# Encodeurs_Schematic.net
KiCad netlist of a schematic drawn in Altium Designer
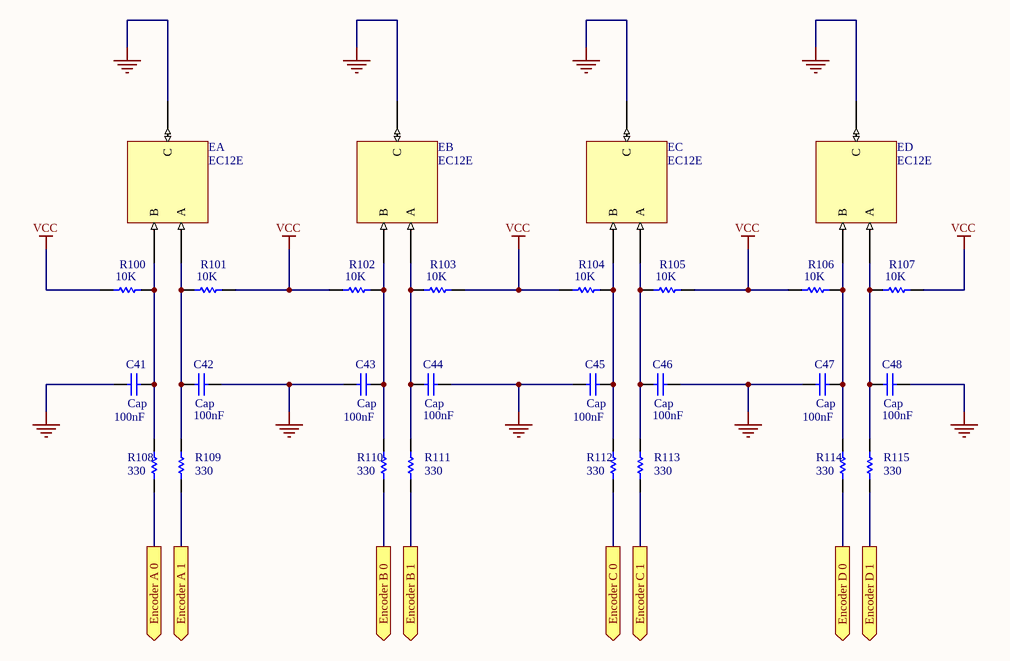
[diagram p0: Encodeurs.Schematic.SchDoc]

(export (version "E")
  (design (tool "Eeschema 10.0.6"))
  (components
    (comp (ref "C41")
      (value "Cap")
      (footprint "CAPC1608N")
      (description "Capacitor")
      (fields (field (name "ALTIUM_VALUE") "100nF") (field (name "PUBLISHER") "Altium Limited"))
      (libsource (lib "Miscellaneous Devices") (part "Cap"))
    )
    (comp (ref "C42")
      (value "Cap")
      (footprint "CAPC1608N")
      (description "Capacitor")
      (fields (field (name "ALTIUM_VALUE") "100nF") (field (name "PUBLISHER") "Altium Limited"))
      (libsource (lib "Miscellaneous Devices") (part "Cap"))
    )
    (comp (ref "C43")
      (value "Cap")
      (footprint "CAPC1608N")
      (description "Capacitor")
      (fields (field (name "ALTIUM_VALUE") "100nF") (field (name "PUBLISHER") "Altium Limited"))
      (libsource (lib "Miscellaneous Devices") (part "Cap"))
    )
    (comp (ref "C44")
      (value "Cap")
      (footprint "CAPC1608N")
      (description "Capacitor")
      (fields (field (name "ALTIUM_VALUE") "100nF") (field (name "PUBLISHER") "Altium Limited"))
      (libsource (lib "Miscellaneous Devices") (part "Cap"))
    )
    (comp (ref "C45")
      (value "Cap")
      (footprint "CAPC1608N")
      (description "Capacitor")
      (fields (field (name "ALTIUM_VALUE") "100nF") (field (name "PUBLISHER") "Altium Limited"))
      (libsource (lib "Miscellaneous Devices") (part "Cap"))
    )
    (comp (ref "C46")
      (value "Cap")
      (footprint "CAPC1608N")
      (description "Capacitor")
      (fields (field (name "ALTIUM_VALUE") "100nF") (field (name "PUBLISHER") "Altium Limited"))
      (libsource (lib "Miscellaneous Devices") (part "Cap"))
    )
    (comp (ref "C47")
      (value "Cap")
      (footprint "CAPC1608N")
      (description "Capacitor")
      (fields (field (name "ALTIUM_VALUE") "100nF") (field (name "PUBLISHER") "Altium Limited"))
      (libsource (lib "Miscellaneous Devices") (part "Cap"))
    )
    (comp (ref "C48")
      (value "Cap")
      (footprint "CAPC1608N")
      (description "Capacitor")
      (fields (field (name "ALTIUM_VALUE") "100nF") (field (name "PUBLISHER") "Altium Limited"))
      (libsource (lib "Miscellaneous Devices") (part "Cap"))
    )
    (comp (ref "EA")
      (value "EC12E")
      (footprint "EC12E")
      (libsource (lib "SynthyTwo.Components") (part "EC12E"))
    )
    (comp (ref "EB")
      (value "EC12E")
      (footprint "EC12E")
      (libsource (lib "SynthyTwo.Components") (part "EC12E"))
    )
    (comp (ref "EC")
      (value "EC12E")
      (footprint "EC12E")
      (libsource (lib "SynthyTwo.Components") (part "EC12E"))
    )
    (comp (ref "ED")
      (value "EC12E")
      (footprint "EC12E")
      (libsource (lib "SynthyTwo.Components") (part "EC12E"))
    )
    (comp (ref "R100")
      (value "10K")
      (footprint "CAPC1608N")
      (description "Resistor")
      (fields (field (name "PUBLISHER") "Altium Limited"))
      (libsource (lib "Miscellaneous Devices") (part "Res1"))
    )
    (comp (ref "R101")
      (value "10K")
      (footprint "CAPC1608N")
      (description "Resistor")
      (fields (field (name "PUBLISHER") "Altium Limited"))
      (libsource (lib "Miscellaneous Devices") (part "Res1"))
    )
    (comp (ref "R102")
      (value "10K")
      (footprint "CAPC1608N")
      (description "Resistor")
      (fields (field (name "PUBLISHER") "Altium Limited"))
      (libsource (lib "Miscellaneous Devices") (part "Res1"))
    )
    (comp (ref "R103")
      (value "10K")
      (footprint "CAPC1608N")
      (description "Resistor")
      (fields (field (name "PUBLISHER") "Altium Limited"))
      (libsource (lib "Miscellaneous Devices") (part "Res1"))
    )
    (comp (ref "R104")
      (value "10K")
      (footprint "CAPC1608N")
      (description "Resistor")
      (fields (field (name "PUBLISHER") "Altium Limited"))
      (libsource (lib "Miscellaneous Devices") (part "Res1"))
    )
    (comp (ref "R105")
      (value "10K")
      (footprint "CAPC1608N")
      (description "Resistor")
      (fields (field (name "PUBLISHER") "Altium Limited"))
      (libsource (lib "Miscellaneous Devices") (part "Res1"))
    )
    (comp (ref "R106")
      (value "10K")
      (footprint "CAPC1608N")
      (description "Resistor")
      (fields (field (name "PUBLISHER") "Altium Limited"))
      (libsource (lib "Miscellaneous Devices") (part "Res1"))
    )
    (comp (ref "R107")
      (value "10K")
      (footprint "CAPC1608N")
      (description "Resistor")
      (fields (field (name "PUBLISHER") "Altium Limited"))
      (libsource (lib "Miscellaneous Devices") (part "Res1"))
    )
    (comp (ref "R108")
      (value "330")
      (footprint "CAPC1608N")
      (description "Resistor")
      (fields (field (name "PUBLISHER") "Altium Limited"))
      (libsource (lib "Miscellaneous Devices") (part "Res1"))
    )
    (comp (ref "R109")
      (value "330")
      (footprint "CAPC1608N")
      (description "Resistor")
      (fields (field (name "PUBLISHER") "Altium Limited"))
      (libsource (lib "Miscellaneous Devices") (part "Res1"))
    )
    (comp (ref "R110")
      (value "330")
      (footprint "CAPC1608N")
      (description "Resistor")
      (fields (field (name "PUBLISHER") "Altium Limited"))
      (libsource (lib "Miscellaneous Devices") (part "Res1"))
    )
    (comp (ref "R111")
      (value "330")
      (footprint "CAPC1608N")
      (description "Resistor")
      (fields (field (name "PUBLISHER") "Altium Limited"))
      (libsource (lib "Miscellaneous Devices") (part "Res1"))
    )
    (comp (ref "R112")
      (value "330")
      (footprint "CAPC1608N")
      (description "Resistor")
      (fields (field (name "PUBLISHER") "Altium Limited"))
      (libsource (lib "Miscellaneous Devices") (part "Res1"))
    )
    (comp (ref "R113")
      (value "330")
      (footprint "CAPC1608N")
      (description "Resistor")
      (fields (field (name "PUBLISHER") "Altium Limited"))
      (libsource (lib "Miscellaneous Devices") (part "Res1"))
    )
    (comp (ref "R114")
      (value "330")
      (footprint "CAPC1608N")
      (description "Resistor")
      (fields (field (name "PUBLISHER") "Altium Limited"))
      (libsource (lib "Miscellaneous Devices") (part "Res1"))
    )
    (comp (ref "R115")
      (value "330")
      (footprint "CAPC1608N")
      (description "Resistor")
      (fields (field (name "PUBLISHER") "Altium Limited"))
      (libsource (lib "Miscellaneous Devices") (part "Res1"))
    )
  )
  (nets
    (net (code "1") (name "/Encoder A 0") (class "Default")
      (node (ref "R108") (pin "1") (pinfunction "1_1") (pintype "passive"))
    )
    (net (code "2") (name "/Encoder A 1") (class "Default")
      (node (ref "R109") (pin "1") (pinfunction "1_1") (pintype "passive"))
    )
    (net (code "3") (name "/Encoder B 0") (class "Default")
      (node (ref "R110") (pin "1") (pinfunction "1_1") (pintype "passive"))
    )
    (net (code "4") (name "/Encoder B 1") (class "Default")
      (node (ref "R111") (pin "1") (pinfunction "1_1") (pintype "passive"))
    )
    (net (code "5") (name "/Encoder C 0") (class "Default")
      (node (ref "R112") (pin "1") (pinfunction "1_1") (pintype "passive"))
    )
    (net (code "6") (name "/Encoder C 1") (class "Default")
      (node (ref "R113") (pin "1") (pinfunction "1_1") (pintype "passive"))
    )
    (net (code "7") (name "/Encoder D 0") (class "Default")
      (node (ref "R114") (pin "1") (pinfunction "1_1") (pintype "passive"))
    )
    (net (code "8") (name "/Encoder D 1") (class "Default")
      (node (ref "R115") (pin "1") (pinfunction "1_1") (pintype "passive"))
    )
    (net (code "9") (name "GND") (class "Default")
      (node (ref "C41") (pin "1") (pinfunction "1_1") (pintype "passive"))
      (node (ref "C42") (pin "1") (pinfunction "1_1") (pintype "passive"))
      (node (ref "C43") (pin "1") (pinfunction "1_1") (pintype "passive"))
      (node (ref "C44") (pin "1") (pinfunction "1_1") (pintype "passive"))
      (node (ref "C45") (pin "1") (pinfunction "1_1") (pintype "passive"))
      (node (ref "C46") (pin "1") (pinfunction "1_1") (pintype "passive"))
      (node (ref "C47") (pin "1") (pinfunction "1_1") (pintype "passive"))
      (node (ref "C48") (pin "1") (pinfunction "1_1") (pintype "passive"))
      (node (ref "EA") (pin "GND") (pinfunction "C_GND") (pintype "bidirectional"))
      (node (ref "EB") (pin "GND") (pinfunction "C_GND") (pintype "bidirectional"))
      (node (ref "EC") (pin "GND") (pinfunction "C_GND") (pintype "bidirectional"))
      (node (ref "ED") (pin "GND") (pinfunction "C_GND") (pintype "bidirectional"))
    )
    (net (code "10") (name "Net-(EA-A)") (class "Default")
      (node (ref "C42") (pin "2") (pinfunction "2_2") (pintype "passive"))
      (node (ref "EA") (pin "Pin_A") (pinfunction "A_Pin_A") (pintype "input"))
      (node (ref "R101") (pin "1") (pinfunction "1_1") (pintype "passive"))
      (node (ref "R109") (pin "2") (pinfunction "2_2") (pintype "passive"))
    )
    (net (code "11") (name "Net-(EA-B)") (class "Default")
      (node (ref "C41") (pin "2") (pinfunction "2_2") (pintype "passive"))
      (node (ref "EA") (pin "Pin_B") (pinfunction "B_Pin_B") (pintype "input"))
      (node (ref "R100") (pin "2") (pinfunction "2_2") (pintype "passive"))
      (node (ref "R108") (pin "2") (pinfunction "2_2") (pintype "passive"))
    )
    (net (code "12") (name "Net-(EB-A)") (class "Default")
      (node (ref "C44") (pin "2") (pinfunction "2_2") (pintype "passive"))
      (node (ref "EB") (pin "Pin_A") (pinfunction "A_Pin_A") (pintype "input"))
      (node (ref "R103") (pin "1") (pinfunction "1_1") (pintype "passive"))
      (node (ref "R111") (pin "2") (pinfunction "2_2") (pintype "passive"))
    )
    (net (code "13") (name "Net-(EB-B)") (class "Default")
      (node (ref "C43") (pin "2") (pinfunction "2_2") (pintype "passive"))
      (node (ref "EB") (pin "Pin_B") (pinfunction "B_Pin_B") (pintype "input"))
      (node (ref "R102") (pin "2") (pinfunction "2_2") (pintype "passive"))
      (node (ref "R110") (pin "2") (pinfunction "2_2") (pintype "passive"))
    )
    (net (code "14") (name "Net-(EC-A)") (class "Default")
      (node (ref "C46") (pin "2") (pinfunction "2_2") (pintype "passive"))
      (node (ref "EC") (pin "Pin_A") (pinfunction "A_Pin_A") (pintype "input"))
      (node (ref "R105") (pin "1") (pinfunction "1_1") (pintype "passive"))
      (node (ref "R113") (pin "2") (pinfunction "2_2") (pintype "passive"))
    )
    (net (code "15") (name "Net-(EC-B)") (class "Default")
      (node (ref "C45") (pin "2") (pinfunction "2_2") (pintype "passive"))
      (node (ref "EC") (pin "Pin_B") (pinfunction "B_Pin_B") (pintype "input"))
      (node (ref "R104") (pin "2") (pinfunction "2_2") (pintype "passive"))
      (node (ref "R112") (pin "2") (pinfunction "2_2") (pintype "passive"))
    )
    (net (code "16") (name "Net-(ED-A)") (class "Default")
      (node (ref "C48") (pin "2") (pinfunction "2_2") (pintype "passive"))
      (node (ref "ED") (pin "Pin_A") (pinfunction "A_Pin_A") (pintype "input"))
      (node (ref "R107") (pin "1") (pinfunction "1_1") (pintype "passive"))
      (node (ref "R115") (pin "2") (pinfunction "2_2") (pintype "passive"))
    )
    (net (code "17") (name "Net-(ED-B)") (class "Default")
      (node (ref "C47") (pin "2") (pinfunction "2_2") (pintype "passive"))
      (node (ref "ED") (pin "Pin_B") (pinfunction "B_Pin_B") (pintype "input"))
      (node (ref "R106") (pin "2") (pinfunction "2_2") (pintype "passive"))
      (node (ref "R114") (pin "2") (pinfunction "2_2") (pintype "passive"))
    )
    (net (code "18") (name "VCC") (class "Default")
      (node (ref "R100") (pin "1") (pinfunction "1_1") (pintype "passive"))
      (node (ref "R101") (pin "2") (pinfunction "2_2") (pintype "passive"))
      (node (ref "R102") (pin "1") (pinfunction "1_1") (pintype "passive"))
      (node (ref "R103") (pin "2") (pinfunction "2_2") (pintype "passive"))
      (node (ref "R104") (pin "1") (pinfunction "1_1") (pintype "passive"))
      (node (ref "R105") (pin "2") (pinfunction "2_2") (pintype "passive"))
      (node (ref "R106") (pin "1") (pinfunction "1_1") (pintype "passive"))
      (node (ref "R107") (pin "2") (pinfunction "2_2") (pintype "passive"))
    )
  )
)
